# PumpkinHardwareV2.net
KiCad netlist of a schematic drawn in EAGLE
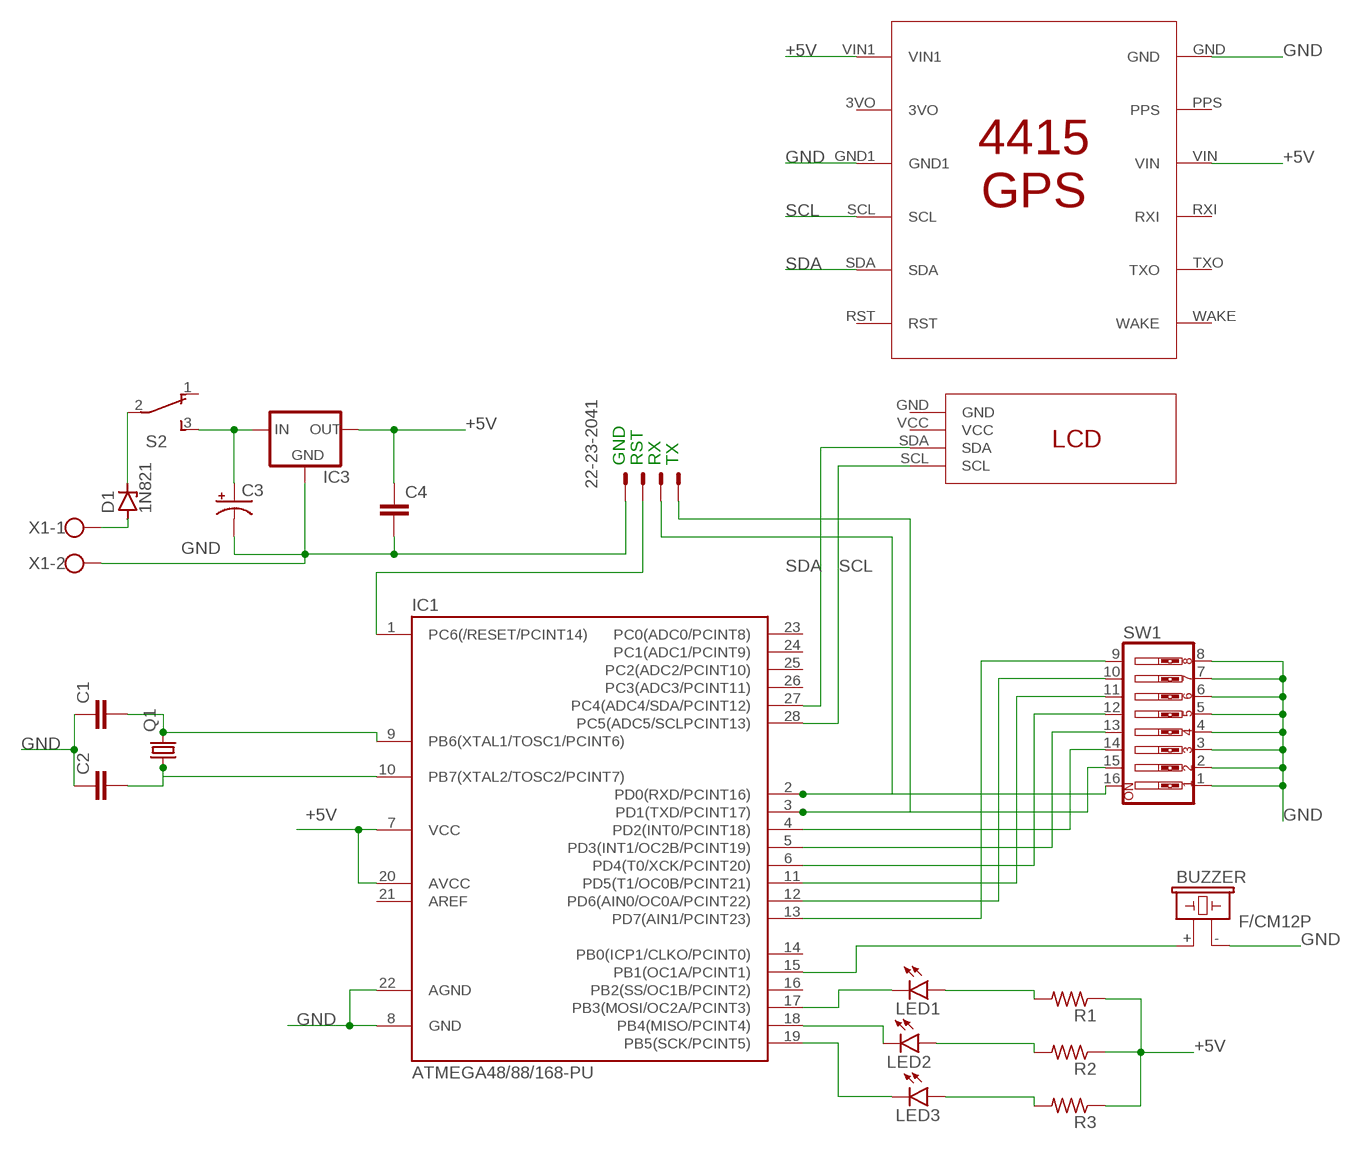
[diagram p0: schematic, sheet 1]

(export (version "E")
  (design (tool "Eeschema 10.0.6"))
  (components
    (comp (ref "BUZZER")
      (value "F/CM12P")
      (footprint "eagle-import:F_CM12P")
      (libsource (lib "eagle-import") (part "F/CM12P"))
    )
    (comp (ref "C1")
      (value "C2.5/2")
      (footprint "eagle-import:C2.5-2")
      (libsource (lib "eagle-import") (part "C2.5/2"))
    )
    (comp (ref "C2")
      (value "C2.5/2")
      (footprint "eagle-import:C2.5-2")
      (libsource (lib "eagle-import") (part "C2.5/2"))
    )
    (comp (ref "C3")
      (value "CPOL-USE3.5-8")
      (footprint "eagle-import:E3,5-8")
      (libsource (lib "eagle-import") (part "CPOL-USE3.5-8"))
    )
    (comp (ref "C4")
      (value "C2.5/2")
      (footprint "eagle-import:C2.5-2")
      (libsource (lib "eagle-import") (part "C2.5/2"))
    )
    (comp (ref "D1")
      (value "1N821")
      (footprint "eagle-import:DO35Z10")
      (libsource (lib "eagle-import") (part "1N821"))
    )
    (comp (ref "GPS")
      (value "4415")
      (footprint "eagle-import:4415")
      (libsource (lib "eagle-import") (part "4415"))
    )
    (comp (ref "IC1")
      (value "ATMEGA48/88/168-PU")
      (footprint "eagle-import:DIL28-3")
      (libsource (lib "eagle-import") (part "ATMEGA48/88/168-PU"))
    )
    (comp (ref "IC3")
      (value "78XXL")
      (footprint "eagle-import:78XXL")
      (libsource (lib "eagle-import") (part "78XXL"))
    )
    (comp (ref "LED1")
      (value "TLLG4400")
      (footprint "eagle-import:LED3MM")
      (fields (field (name "MF") "VISHAY SEMICONDUCTOR"))
      (libsource (lib "eagle-import") (part "TLLG4400"))
    )
    (comp (ref "LED2")
      (value "TLLY4400")
      (footprint "eagle-import:LED3MM")
      (fields (field (name "MF") "VISHAY SEMICONDUCTOR"))
      (libsource (lib "eagle-import") (part "TLLY4400"))
    )
    (comp (ref "LED3")
      (value "TLLR4400")
      (footprint "eagle-import:LED3MM")
      (fields (field (name "MF") "VISHAY SEMICONDUCTOR"))
      (libsource (lib "eagle-import") (part "TLLR4400"))
    )
    (comp (ref "Q1")
      (value "CRYSTALHC49S")
      (footprint "eagle-import:HC49_S")
      (libsource (lib "eagle-import") (part "CRYSTALHC49S"))
    )
    (comp (ref "R1")
      (value "R-US_0207/10")
      (footprint "eagle-import:0207_10")
      (libsource (lib "eagle-import") (part "R-US_0207/10"))
    )
    (comp (ref "R2")
      (value "R-US_0207/10")
      (footprint "eagle-import:0207_10")
      (libsource (lib "eagle-import") (part "R-US_0207/10"))
    )
    (comp (ref "R3")
      (value "R-US_0207/10")
      (footprint "eagle-import:0207_10")
      (libsource (lib "eagle-import") (part "R-US_0207/10"))
    )
    (comp (ref "S2")
      (value "TL36PO")
      (footprint "eagle-import:TL3XPO")
      (libsource (lib "eagle-import") (part "TL36PO"))
    )
    (comp (ref "SW1")
      (value "SW_DIP-8")
      (footprint "eagle-import:EDG-08")
      (libsource (lib "eagle-import") (part "SW_DIP-8"))
    )
    (comp (ref "U$1")
      (value "I2C_LCD")
      (footprint "eagle-import:I2C_LCD")
      (libsource (lib "eagle-import") (part "I2C_LCD"))
    )
    (comp (ref "X1")
      (value "W237-102")
      (footprint "eagle-import:W237-102")
      (fields (field (name "MPN") "237-102"))
      (libsource (lib "eagle-import") (part "W237-102"))
    )
    (comp (ref "X2")
      (value "22-23-2041")
      (footprint "eagle-import:22-23-2041")
      (fields (field (name "MF") "MOLEX"))
      (libsource (lib "eagle-import") (part "22-23-2041"))
    )
  )
  (nets
    (net (code "1") (name "/+5V") (class "Default")
      (node (ref "C4") (pin "1") (pinfunction "1_1") (pintype "passive"))
      (node (ref "GPS") (pin "VIN") (pinfunction "VIN_VIN") (pintype "bidirectional"))
      (node (ref "GPS") (pin "VIN1") (pinfunction "VIN1_VIN1") (pintype "bidirectional"))
      (node (ref "IC1") (pin "20") (pinfunction "AVCC_20") (pintype "passive"))
      (node (ref "IC1") (pin "7") (pinfunction "VCC_7") (pintype "power_in"))
      (node (ref "IC3") (pin "OUT") (pinfunction "OUT_OUT") (pintype "passive"))
      (node (ref "R1") (pin "1") (pinfunction "1_1") (pintype "passive"))
      (node (ref "R2") (pin "1") (pinfunction "1_1") (pintype "passive"))
      (node (ref "R3") (pin "1") (pinfunction "1_1") (pintype "passive"))
    )
    (net (code "2") (name "/GND") (class "Default")
      (node (ref "BUZZER") (pin "-") (pinfunction "2_-") (pintype "passive"))
      (node (ref "C1") (pin "1") (pinfunction "1_1") (pintype "passive"))
      (node (ref "C2") (pin "1") (pinfunction "1_1") (pintype "passive"))
      (node (ref "C3") (pin "-") (pinfunction "-_-") (pintype "passive"))
      (node (ref "C4") (pin "2") (pinfunction "2_2") (pintype "passive"))
      (node (ref "GPS") (pin "GND") (pinfunction "GND_GND") (pintype "bidirectional"))
      (node (ref "GPS") (pin "GND1") (pinfunction "GND1_GND1") (pintype "bidirectional"))
      (node (ref "IC1") (pin "22") (pinfunction "AGND_22") (pintype "power_in"))
      (node (ref "IC1") (pin "8") (pinfunction "GND_8") (pintype "power_in"))
      (node (ref "IC3") (pin "GND") (pinfunction "GND_GND") (pintype "input"))
      (node (ref "SW1") (pin "1") (pinfunction "1_1") (pintype "passive"))
      (node (ref "SW1") (pin "2") (pinfunction "2_2") (pintype "passive"))
      (node (ref "SW1") (pin "3") (pinfunction "3_3") (pintype "passive"))
      (node (ref "SW1") (pin "4") (pinfunction "4_4") (pintype "passive"))
      (node (ref "SW1") (pin "5") (pinfunction "5_5") (pintype "passive"))
      (node (ref "SW1") (pin "6") (pinfunction "6_6") (pintype "passive"))
      (node (ref "SW1") (pin "7") (pinfunction "7_7") (pintype "passive"))
      (node (ref "SW1") (pin "8") (pinfunction "8_8") (pintype "passive"))
      (node (ref "X1") (pin "2") (pinfunction "KL_2") (pintype "passive"))
      (node (ref "X2") (pin "1") (pinfunction "S_1") (pintype "passive"))
    )
    (net (code "3") (name "/SCL") (class "Default")
      (node (ref "GPS") (pin "SCL") (pinfunction "SCL_SCL") (pintype "bidirectional"))
      (node (ref "IC1") (pin "28") (pinfunction "PC5(ADC5/SCLPCINT13)_28") (pintype "bidirectional"))
      (node (ref "U$1") (pin "SCL") (pinfunction "SCL_SCL") (pintype "bidirectional"))
    )
    (net (code "4") (name "/SDA") (class "Default")
      (node (ref "GPS") (pin "SDA") (pinfunction "SDA_SDA") (pintype "bidirectional"))
      (node (ref "IC1") (pin "27") (pinfunction "PC4(ADC4/SDA/PCINT12)_27") (pintype "bidirectional"))
      (node (ref "U$1") (pin "SDA") (pinfunction "SDA_SDA") (pintype "bidirectional"))
    )
    (net (code "5") (name "Net-(BUZZER-1)") (class "Default")
      (node (ref "BUZZER") (pin "+") (pinfunction "1_+") (pintype "passive"))
      (node (ref "IC1") (pin "15") (pinfunction "PB1(OC1A/PCINT1)_15") (pintype "bidirectional"))
    )
    (net (code "6") (name "Net-(IC1-PB3(MOSI{slash}OC2A{slash}PCINT3))") (class "Default")
      (node (ref "IC1") (pin "17") (pinfunction "PB3(MOSI/OC2A/PCINT3)_17") (pintype "bidirectional"))
      (node (ref "LED1") (pin "K") (pinfunction "C_K") (pintype "passive"))
    )
    (net (code "7") (name "Net-(IC1-PB4(MISO{slash}PCINT4))") (class "Default")
      (node (ref "IC1") (pin "18") (pinfunction "PB4(MISO/PCINT4)_18") (pintype "bidirectional"))
      (node (ref "LED2") (pin "K") (pinfunction "C_K") (pintype "passive"))
    )
    (net (code "8") (name "Net-(IC1-PB5(SCK{slash}PCINT5))") (class "Default")
      (node (ref "IC1") (pin "19") (pinfunction "PB5(SCK/PCINT5)_19") (pintype "bidirectional"))
      (node (ref "LED3") (pin "K") (pinfunction "C_K") (pintype "passive"))
    )
    (net (code "9") (name "Net-(IC1-PB6(XTAL1{slash}TOSC1{slash}PCINT6))") (class "Default")
      (node (ref "C1") (pin "2") (pinfunction "2_2") (pintype "passive"))
      (node (ref "IC1") (pin "9") (pinfunction "PB6(XTAL1/TOSC1/PCINT6)_9") (pintype "bidirectional"))
      (node (ref "Q1") (pin "2") (pinfunction "2_2") (pintype "passive"))
    )
    (net (code "10") (name "Net-(IC1-PB7(XTAL2{slash}TOSC2{slash}PCINT7))") (class "Default")
      (node (ref "C2") (pin "2") (pinfunction "2_2") (pintype "passive"))
      (node (ref "IC1") (pin "10") (pinfunction "PB7(XTAL2/TOSC2/PCINT7)_10") (pintype "bidirectional"))
      (node (ref "Q1") (pin "1") (pinfunction "1_1") (pintype "passive"))
    )
    (net (code "11") (name "Net-(IC1-PC6({slash}RESET{slash}PCINT14))") (class "Default")
      (node (ref "IC1") (pin "1") (pinfunction "PC6(/RESET/PCINT14)_1") (pintype "bidirectional"))
      (node (ref "X2") (pin "2") (pinfunction "S_2") (pintype "passive"))
    )
    (net (code "12") (name "Net-(IC1-PD0(RXD{slash}PCINT16))") (class "Default")
      (node (ref "IC1") (pin "2") (pinfunction "PD0(RXD/PCINT16)_2") (pintype "bidirectional"))
      (node (ref "SW1") (pin "16") (pinfunction "16_16") (pintype "passive"))
      (node (ref "X2") (pin "3") (pinfunction "S_3") (pintype "passive"))
    )
    (net (code "13") (name "Net-(IC1-PD1(TXD{slash}PCINT17))") (class "Default")
      (node (ref "IC1") (pin "3") (pinfunction "PD1(TXD/PCINT17)_3") (pintype "bidirectional"))
      (node (ref "SW1") (pin "15") (pinfunction "15_15") (pintype "passive"))
      (node (ref "X2") (pin "4") (pinfunction "S_4") (pintype "passive"))
    )
    (net (code "14") (name "Net-(IC1-PD2(INT0{slash}PCINT18))") (class "Default")
      (node (ref "IC1") (pin "4") (pinfunction "PD2(INT0/PCINT18)_4") (pintype "bidirectional"))
      (node (ref "SW1") (pin "14") (pinfunction "14_14") (pintype "passive"))
    )
    (net (code "15") (name "Net-(IC1-PD3(INT1{slash}OC2B{slash}PCINT19))") (class "Default")
      (node (ref "IC1") (pin "5") (pinfunction "PD3(INT1/OC2B/PCINT19)_5") (pintype "bidirectional"))
      (node (ref "SW1") (pin "13") (pinfunction "13_13") (pintype "passive"))
    )
    (net (code "16") (name "Net-(IC1-PD4(T0{slash}XCK{slash}PCINT20))") (class "Default")
      (node (ref "IC1") (pin "6") (pinfunction "PD4(T0/XCK/PCINT20)_6") (pintype "bidirectional"))
      (node (ref "SW1") (pin "12") (pinfunction "12_12") (pintype "passive"))
    )
    (net (code "17") (name "Net-(IC1-PD5(T1{slash}OC0B{slash}PCINT21))") (class "Default")
      (node (ref "IC1") (pin "11") (pinfunction "PD5(T1/OC0B/PCINT21)_11") (pintype "bidirectional"))
      (node (ref "SW1") (pin "11") (pinfunction "11_11") (pintype "passive"))
    )
    (net (code "18") (name "Net-(IC1-PD6(AIN0{slash}OC0A{slash}PCINT22))") (class "Default")
      (node (ref "IC1") (pin "12") (pinfunction "PD6(AIN0/OC0A/PCINT22)_12") (pintype "bidirectional"))
      (node (ref "SW1") (pin "10") (pinfunction "10_10") (pintype "passive"))
    )
    (net (code "19") (name "Net-(IC1-PD7(AIN1{slash}PCINT23))") (class "Default")
      (node (ref "IC1") (pin "13") (pinfunction "PD7(AIN1/PCINT23)_13") (pintype "bidirectional"))
      (node (ref "SW1") (pin "9") (pinfunction "9_9") (pintype "passive"))
    )
    (net (code "20") (name "Net-(LED1-PadA)") (class "Default")
      (node (ref "LED1") (pin "A") (pinfunction "A_A") (pintype "passive"))
      (node (ref "R1") (pin "2") (pinfunction "2_2") (pintype "passive"))
    )
    (net (code "21") (name "Net-(LED2-PadA)") (class "Default")
      (node (ref "LED2") (pin "A") (pinfunction "A_A") (pintype "passive"))
      (node (ref "R2") (pin "2") (pinfunction "2_2") (pintype "passive"))
    )
    (net (code "22") (name "Net-(LED3-PadA)") (class "Default")
      (node (ref "LED3") (pin "A") (pinfunction "A_A") (pintype "passive"))
      (node (ref "R3") (pin "2") (pinfunction "2_2") (pintype "passive"))
    )
    (net (code "23") (name "Net-(S2-P)") (class "Default")
      (node (ref "D1") (pin "C") (pinfunction "C_C") (pintype "passive"))
      (node (ref "S2") (pin "2") (pinfunction "P_2") (pintype "passive"))
    )
    (net (code "24") (name "Net-(S2-S)") (class "Default")
      (node (ref "C3") (pin "+") (pinfunction "+_+") (pintype "passive"))
      (node (ref "IC3") (pin "IN") (pinfunction "IN_IN") (pintype "input"))
      (node (ref "S2") (pin "3") (pinfunction "S_3") (pintype "passive"))
    )
    (net (code "25") (name "Net-(X1A-KL)") (class "Default")
      (node (ref "D1") (pin "A") (pinfunction "A_A") (pintype "passive"))
      (node (ref "X1") (pin "1") (pinfunction "KL_1") (pintype "passive"))
    )
    (net (code "26") (name "unconnected-(GPS-Pad3VO)") (class "Default")
      (node (ref "GPS") (pin "3VO") (pinfunction "3VO_3VO") (pintype "bidirectional"))
    )
    (net (code "27") (name "unconnected-(GPS-PadPPS)") (class "Default")
      (node (ref "GPS") (pin "PPS") (pinfunction "PPS_PPS") (pintype "bidirectional"))
    )
    (net (code "28") (name "unconnected-(GPS-PadRST)") (class "Default")
      (node (ref "GPS") (pin "RST") (pinfunction "RST_RST") (pintype "bidirectional"))
    )
    (net (code "29") (name "unconnected-(GPS-PadRXI)") (class "Default")
      (node (ref "GPS") (pin "RXI") (pinfunction "RXI_RXI") (pintype "bidirectional"))
    )
    (net (code "30") (name "unconnected-(GPS-PadTXO)") (class "Default")
      (node (ref "GPS") (pin "TXO") (pinfunction "TXO_TXO") (pintype "bidirectional"))
    )
    (net (code "31") (name "unconnected-(GPS-PadWAKE)") (class "Default")
      (node (ref "GPS") (pin "WAKE") (pinfunction "WAKE_WAKE") (pintype "bidirectional"))
    )
    (net (code "32") (name "unconnected-(IC1-AREF-Pad21)") (class "Default")
      (node (ref "IC1") (pin "21") (pinfunction "AREF_21") (pintype "passive"))
    )
    (net (code "33") (name "unconnected-(IC1-PB0(ICP1{slash}CLKO{slash}PCINT0)-Pad14)") (class "Default")
      (node (ref "IC1") (pin "14") (pinfunction "PB0(ICP1/CLKO/PCINT0)_14") (pintype "bidirectional"))
    )
    (net (code "34") (name "unconnected-(IC1-PB2(SS{slash}OC1B{slash}PCINT2)-Pad16)") (class "Default")
      (node (ref "IC1") (pin "16") (pinfunction "PB2(SS/OC1B/PCINT2)_16") (pintype "bidirectional"))
    )
    (net (code "35") (name "unconnected-(IC1-PC0(ADC0{slash}PCINT8)-Pad23)") (class "Default")
      (node (ref "IC1") (pin "23") (pinfunction "PC0(ADC0/PCINT8)_23") (pintype "bidirectional"))
    )
    (net (code "36") (name "unconnected-(IC1-PC1(ADC1{slash}PCINT9)-Pad24)") (class "Default")
      (node (ref "IC1") (pin "24") (pinfunction "PC1(ADC1/PCINT9)_24") (pintype "bidirectional"))
    )
    (net (code "37") (name "unconnected-(IC1-PC2(ADC2{slash}PCINT10)-Pad25)") (class "Default")
      (node (ref "IC1") (pin "25") (pinfunction "PC2(ADC2/PCINT10)_25") (pintype "bidirectional"))
    )
    (net (code "38") (name "unconnected-(IC1-PC3(ADC3{slash}PCINT11)-Pad26)") (class "Default")
      (node (ref "IC1") (pin "26") (pinfunction "PC3(ADC3/PCINT11)_26") (pintype "bidirectional"))
    )
    (net (code "39") (name "unconnected-(S2-O-Pad1)") (class "Default")
      (node (ref "S2") (pin "1") (pinfunction "O_1") (pintype "passive"))
    )
    (net (code "40") (name "unconnected-(U$1-PadGND)") (class "Default")
      (node (ref "U$1") (pin "GND") (pinfunction "GND_GND") (pintype "bidirectional"))
    )
    (net (code "41") (name "unconnected-(U$1-PadVCC)") (class "Default")
      (node (ref "U$1") (pin "VCC") (pinfunction "VCC_VCC") (pintype "bidirectional"))
    )
  )
)
